# v1.net
KiCad netlist of a schematic drawn in EAGLE
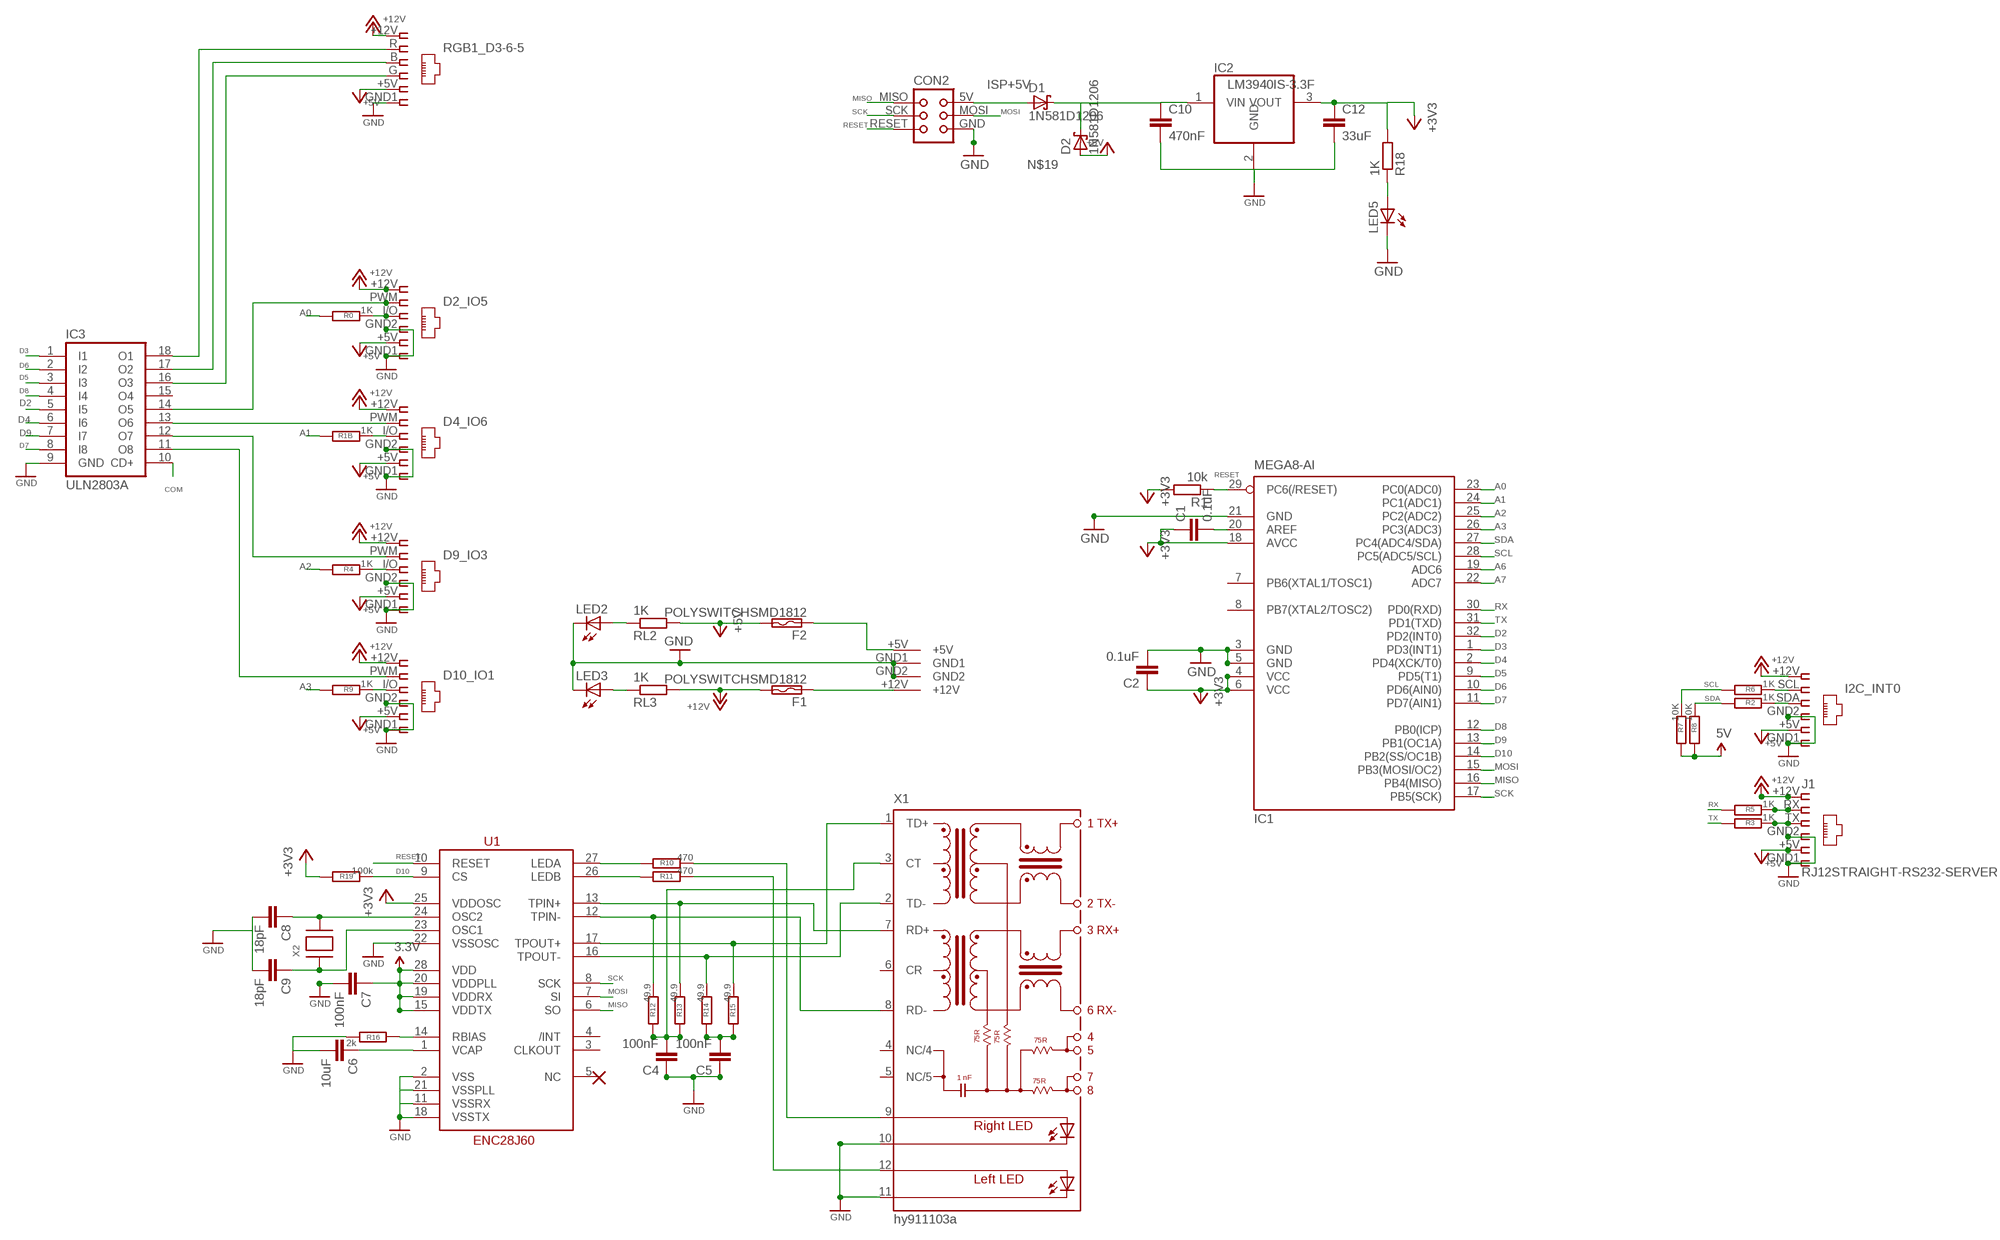
[diagram p0: schematic, sheet 1]

(export (version "E")
  (design (tool "Eeschema 10.0.6"))
  (components
    (comp (ref "C1")
      (value "0.1uF")
      (footprint "eagle-import:C1206")
      (libsource (lib "eagle-import") (part "resistor_C-EUC1206"))
    )
    (comp (ref "C2")
      (value "0.1uF")
      (footprint "eagle-import:C1206")
      (libsource (lib "eagle-import") (part "resistor_C-EUC1206"))
    )
    (comp (ref "C4")
      (value "100nF")
      (footprint "eagle-import:C1206")
      (libsource (lib "eagle-import") (part "resistor_C-EUC1206"))
    )
    (comp (ref "C5")
      (value "100nF")
      (footprint "eagle-import:C1206")
      (libsource (lib "eagle-import") (part "resistor_C-EUC1206"))
    )
    (comp (ref "C6")
      (value "10uF")
      (footprint "eagle-import:C1206")
      (libsource (lib "eagle-import") (part "resistor_C-EUC1206"))
    )
    (comp (ref "C7")
      (value "100nF")
      (footprint "eagle-import:C1206")
      (libsource (lib "eagle-import") (part "resistor_C-EUC1206"))
    )
    (comp (ref "C8")
      (value "18pF")
      (footprint "eagle-import:C1206")
      (libsource (lib "eagle-import") (part "resistor_C-EUC1206"))
    )
    (comp (ref "C9")
      (value "18pF")
      (footprint "eagle-import:C1206")
      (libsource (lib "eagle-import") (part "resistor_C-EUC1206"))
    )
    (comp (ref "C10")
      (value "470nF")
      (footprint "eagle-import:C1206")
      (libsource (lib "eagle-import") (part "C-EUC1206"))
    )
    (comp (ref "C12")
      (value "33uF")
      (footprint "eagle-import:1210")
      (libsource (lib "eagle-import") (part "CAP1210"))
    )
    (comp (ref "CON2")
      (value "TINYISPTAG")
      (footprint "eagle-import:TC2030-MCP")
      (libsource (lib "eagle-import") (part "TINYISPTAG"))
    )
    (comp (ref "D1")
      (value "1N581D1206")
      (footprint "eagle-import:LED-1206")
      (libsource (lib "eagle-import") (part "1N581D1206"))
    )
    (comp (ref "D2")
      (value "1N581D1206")
      (footprint "eagle-import:LED-1206")
      (libsource (lib "eagle-import") (part "1N581D1206"))
    )
    (comp (ref "D2_IO5")
      (value "IO5")
      (footprint "eagle-import:RJ12-STRAIGHT")
      (libsource (lib "eagle-import") (part "RJ12STRAIGHT"))
    )
    (comp (ref "D4_IO6")
      (value "IO6")
      (footprint "eagle-import:RJ12-STRAIGHT")
      (libsource (lib "eagle-import") (part "RJ12STRAIGHT"))
    )
    (comp (ref "D9_IO3")
      (value "IO3")
      (footprint "eagle-import:RJ12-STRAIGHT")
      (libsource (lib "eagle-import") (part "RJ12STRAIGHT"))
    )
    (comp (ref "D10_IO1")
      (value "IO1")
      (footprint "eagle-import:RJ12-STRAIGHT")
      (libsource (lib "eagle-import") (part "RJ12STRAIGHT"))
    )
    (comp (ref "F1")
      (value "POLYSWITCHSMD1812")
      (footprint "eagle-import:C1812")
      (libsource (lib "eagle-import") (part "POLYSWITCHSMD1812"))
    )
    (comp (ref "F2")
      (value "POLYSWITCHSMD1812")
      (footprint "eagle-import:C1812")
      (libsource (lib "eagle-import") (part "POLYSWITCHSMD1812"))
    )
    (comp (ref "I2C_INT0")
      (value "I2C")
      (footprint "eagle-import:RJ12-STRAIGHT-I2C")
      (libsource (lib "eagle-import") (part "RJ12STRAIGHT-I2C"))
    )
    (comp (ref "IC1")
      (value "MEGA8-AI")
      (footprint "eagle-import:TQFP32-08")
      (fields (field (name "MPN") "ATMEGA8-16AU"))
      (libsource (lib "eagle-import") (part "MEGA8-AI"))
    )
    (comp (ref "IC2")
      (value "LM3940IS-3.3F")
      (footprint "eagle-import:DD-3")
      (fields (field (name "MF") "TEXAS INSTRUMENTS") (field (name "MPN") "REG1117FAKTTT"))
      (libsource (lib "eagle-import") (part "LM3940IS-3.3F"))
    )
    (comp (ref "IC3")
      (value "ULN2803A")
      (footprint "eagle-import:SO18W")
      (libsource (lib "eagle-import") (part "ULN2803A"))
    )
    (comp (ref "J1")
      (value "RJ12STRAIGHT-RS232-SERVER")
      (footprint "eagle-import:RJ12-STRAIGHT-RS232")
      (libsource (lib "eagle-import") (part "RJ12STRAIGHT-RS232-SERVER"))
    )
    (comp (ref "LED2")
      (value "LED3MM")
      (footprint "eagle-import:LED3MM")
      (libsource (lib "eagle-import") (part "LED3MM"))
    )
    (comp (ref "LED3")
      (value "LED3MM")
      (footprint "eagle-import:LED3MM")
      (libsource (lib "eagle-import") (part "LED3MM"))
    )
    (comp (ref "LED5")
      (value "LED3MM")
      (footprint "eagle-import:LED3MM")
      (libsource (lib "eagle-import") (part "LED3MM"))
    )
    (comp (ref "R0")
      (value "1K")
      (footprint "eagle-import:M1206")
      (libsource (lib "eagle-import") (part "R-EU_M1206"))
    )
    (comp (ref "R1")
      (value "10k")
      (footprint "eagle-import:M1206")
      (libsource (lib "eagle-import") (part "R-EU_M1206"))
    )
    (comp (ref "R1B")
      (value "1K")
      (footprint "eagle-import:M1206")
      (libsource (lib "eagle-import") (part "R-EU_M1206"))
    )
    (comp (ref "R2")
      (value "1K")
      (footprint "eagle-import:M1206")
      (libsource (lib "eagle-import") (part "R-EU_M1206"))
    )
    (comp (ref "R3")
      (value "1K")
      (footprint "eagle-import:M1206")
      (libsource (lib "eagle-import") (part "R-EU_M1206"))
    )
    (comp (ref "R4")
      (value "1K")
      (footprint "eagle-import:M1206")
      (libsource (lib "eagle-import") (part "R-EU_M1206"))
    )
    (comp (ref "R5")
      (value "1K")
      (footprint "eagle-import:M1206")
      (libsource (lib "eagle-import") (part "R-EU_M1206"))
    )
    (comp (ref "R6")
      (value "1K")
      (footprint "eagle-import:M1206")
      (libsource (lib "eagle-import") (part "R-EU_M1206"))
    )
    (comp (ref "R7")
      (value "10K")
      (footprint "eagle-import:M1206")
      (libsource (lib "eagle-import") (part "R-EU_M1206"))
    )
    (comp (ref "R8")
      (value "10K")
      (footprint "eagle-import:M1206")
      (libsource (lib "eagle-import") (part "R-EU_M1206"))
    )
    (comp (ref "R9")
      (value "1K")
      (footprint "eagle-import:M1206")
      (libsource (lib "eagle-import") (part "R-EU_M1206"))
    )
    (comp (ref "R10")
      (value "470")
      (footprint "eagle-import:M1206")
      (libsource (lib "eagle-import") (part "R-EU_M1206"))
    )
    (comp (ref "R11")
      (value "470")
      (footprint "eagle-import:M1206")
      (libsource (lib "eagle-import") (part "R-EU_M1206"))
    )
    (comp (ref "R12")
      (value "49.9")
      (footprint "eagle-import:M1206")
      (libsource (lib "eagle-import") (part "R-EU_M1206"))
    )
    (comp (ref "R13")
      (value "49.9")
      (footprint "eagle-import:M1206")
      (libsource (lib "eagle-import") (part "R-EU_M1206"))
    )
    (comp (ref "R14")
      (value "49.9")
      (footprint "eagle-import:M1206")
      (libsource (lib "eagle-import") (part "R-EU_M1206"))
    )
    (comp (ref "R15")
      (value "49.9")
      (footprint "eagle-import:M1206")
      (libsource (lib "eagle-import") (part "R-EU_M1206"))
    )
    (comp (ref "R16")
      (value "2k")
      (footprint "eagle-import:M1206")
      (libsource (lib "eagle-import") (part "R-EU_M1206"))
    )
    (comp (ref "R18")
      (value "1K")
      (footprint "eagle-import:M1206")
      (libsource (lib "eagle-import") (part "R-EU_M1206"))
    )
    (comp (ref "R19")
      (value "100k")
      (footprint "eagle-import:M1206")
      (libsource (lib "eagle-import") (part "R-EU_M1206"))
    )
    (comp (ref "RGB1_D3-6-5")
      (value "RGB1")
      (footprint "eagle-import:RJ12-STRAIGHT-RGB")
      (libsource (lib "eagle-import") (part "RJ12STRAIGHT-RGB"))
    )
    (comp (ref "RL2")
      (value "1K")
      (footprint "eagle-import:M1206")
      (libsource (lib "eagle-import") (part "R-EU_M1206"))
    )
    (comp (ref "RL3")
      (value "1K")
      (footprint "eagle-import:M1206")
      (libsource (lib "eagle-import") (part "R-EU_M1206"))
    )
    (comp (ref "U$2")
      (value "KPJX-4S-S")
      (footprint "eagle-import:KPJX-4S-S")
      (libsource (lib "eagle-import") (part "KPJX-4S-S"))
    )
    (comp (ref "U1")
      (value "ENC28J60SO")
      (footprint "eagle-import:SO28W")
      (libsource (lib "eagle-import") (part "ENC28J60SO"))
    )
    (comp (ref "X1")
      (value "hy911103a")
      (footprint "eagle-import:J1")
      (libsource (lib "eagle-import") (part "J1011F01P"))
    )
    (comp (ref "X2")
      (value "XTALNX5032")
      (footprint "eagle-import:NX5032")
      (libsource (lib "eagle-import") (part "XTALNX5032"))
    )
  )
  (nets
    (net (code "1") (name "+3V3") (class "Default")
      (node (ref "C1") (pin "1") (pinfunction "1_1") (pintype "passive"))
      (node (ref "C12") (pin "1") (pinfunction "1_1") (pintype "passive"))
      (node (ref "C2") (pin "1") (pinfunction "1_1") (pintype "passive"))
      (node (ref "IC1") (pin "18") (pinfunction "AVCC_18") (pintype "power_in"))
      (node (ref "IC1") (pin "4") (pinfunction "VCC_4") (pintype "power_in"))
      (node (ref "IC1") (pin "6") (pinfunction "VCC_6") (pintype "power_in"))
      (node (ref "IC2") (pin "3") (pinfunction "VOUT_3") (pintype "output"))
      (node (ref "R1") (pin "2") (pinfunction "2_2") (pintype "passive"))
      (node (ref "R18") (pin "2") (pinfunction "2_2") (pintype "passive"))
      (node (ref "R19") (pin "2") (pinfunction "2_2") (pintype "passive"))
      (node (ref "U1") (pin "25") (pinfunction "VDDOSC_25") (pintype "bidirectional"))
    )
    (net (code "2") (name "+5V") (class "Default")
      (node (ref "D10_IO1") (pin "+5V") (pinfunction "5_+5V") (pintype "power_in"))
      (node (ref "D2") (pin "A") (pinfunction "A_A") (pintype "passive"))
      (node (ref "D2_IO5") (pin "+5V") (pinfunction "5_+5V") (pintype "power_in"))
      (node (ref "D4_IO6") (pin "+5V") (pinfunction "5_+5V") (pintype "power_in"))
      (node (ref "D9_IO3") (pin "+5V") (pinfunction "5_+5V") (pintype "power_in"))
      (node (ref "F2") (pin "2") (pinfunction "2_2") (pintype "passive"))
      (node (ref "I2C_INT0") (pin "+5V") (pinfunction "5_+5V") (pintype "power_in"))
      (node (ref "J1") (pin "+5V") (pinfunction "5_+5V") (pintype "power_in"))
      (node (ref "RGB1_D3-6-5") (pin "+5V") (pinfunction "5_+5V") (pintype "power_in"))
      (node (ref "RL2") (pin "2") (pinfunction "2_2") (pintype "passive"))
    )
    (net (code "3") (name "+12V") (class "Default")
      (node (ref "D10_IO1") (pin "+12V") (pinfunction "1_+12V") (pintype "power_in"))
      (node (ref "D2_IO5") (pin "+12V") (pinfunction "1_+12V") (pintype "power_in"))
      (node (ref "D4_IO6") (pin "+12V") (pinfunction "1_+12V") (pintype "power_in"))
      (node (ref "D9_IO3") (pin "+12V") (pinfunction "1_+12V") (pintype "power_in"))
      (node (ref "F1") (pin "2") (pinfunction "2_2") (pintype "passive"))
      (node (ref "I2C_INT0") (pin "+12V") (pinfunction "1_+12V") (pintype "power_in"))
      (node (ref "J1") (pin "+12V") (pinfunction "1_+12V") (pintype "power_in"))
      (node (ref "RGB1_D3-6-5") (pin "+12V") (pinfunction "1_+12V") (pintype "power_in"))
      (node (ref "RL3") (pin "2") (pinfunction "2_2") (pintype "passive"))
    )
    (net (code "4") (name "/A0") (class "Default")
      (node (ref "IC1") (pin "23") (pinfunction "PC0(ADC0)_23") (pintype "bidirectional"))
      (node (ref "R0") (pin "2") (pinfunction "2_2") (pintype "passive"))
    )
    (net (code "5") (name "/A1") (class "Default")
      (node (ref "IC1") (pin "24") (pinfunction "PC1(ADC1)_24") (pintype "bidirectional"))
      (node (ref "R1B") (pin "2") (pinfunction "2_2") (pintype "passive"))
    )
    (net (code "6") (name "/A2") (class "Default")
      (node (ref "IC1") (pin "25") (pinfunction "PC2(ADC2)_25") (pintype "bidirectional"))
      (node (ref "R4") (pin "2") (pinfunction "2_2") (pintype "passive"))
    )
    (net (code "7") (name "/A3") (class "Default")
      (node (ref "IC1") (pin "26") (pinfunction "PC3(ADC3)_26") (pintype "bidirectional"))
      (node (ref "R9") (pin "2") (pinfunction "2_2") (pintype "passive"))
    )
    (net (code "8") (name "/A6") (class "Default")
      (node (ref "IC1") (pin "19") (pinfunction "ADC6_19") (pintype "bidirectional"))
    )
    (net (code "9") (name "/A7") (class "Default")
      (node (ref "IC1") (pin "22") (pinfunction "ADC7_22") (pintype "bidirectional"))
    )
    (net (code "10") (name "/COM") (class "Default")
      (node (ref "IC3") (pin "10") (pinfunction "CD+_10") (pintype "passive"))
    )
    (net (code "11") (name "/D2") (class "Default")
      (node (ref "IC1") (pin "32") (pinfunction "PD2(INT0)_32") (pintype "bidirectional"))
      (node (ref "IC3") (pin "5") (pinfunction "I5_5") (pintype "input"))
    )
    (net (code "12") (name "/D3") (class "Default")
      (node (ref "IC1") (pin "1") (pinfunction "PD3(INT1)_1") (pintype "bidirectional"))
      (node (ref "IC3") (pin "1") (pinfunction "I1_1") (pintype "input"))
    )
    (net (code "13") (name "/D4") (class "Default")
      (node (ref "IC1") (pin "2") (pinfunction "PD4(XCK/T0)_2") (pintype "bidirectional"))
      (node (ref "IC3") (pin "6") (pinfunction "I6_6") (pintype "input"))
    )
    (net (code "14") (name "/D5") (class "Default")
      (node (ref "IC1") (pin "9") (pinfunction "PD5(T1)_9") (pintype "bidirectional"))
      (node (ref "IC3") (pin "3") (pinfunction "I3_3") (pintype "input"))
    )
    (net (code "15") (name "/D6") (class "Default")
      (node (ref "IC1") (pin "10") (pinfunction "PD6(AIN0)_10") (pintype "bidirectional"))
      (node (ref "IC3") (pin "2") (pinfunction "I2_2") (pintype "input"))
    )
    (net (code "16") (name "/D7") (class "Default")
      (node (ref "IC1") (pin "11") (pinfunction "PD7(AIN1)_11") (pintype "bidirectional"))
      (node (ref "IC3") (pin "8") (pinfunction "I8_8") (pintype "input"))
    )
    (net (code "17") (name "/D8") (class "Default")
      (node (ref "IC1") (pin "12") (pinfunction "PB0(ICP)_12") (pintype "bidirectional"))
      (node (ref "IC3") (pin "4") (pinfunction "I4_4") (pintype "input"))
    )
    (net (code "18") (name "/D9") (class "Default")
      (node (ref "IC1") (pin "13") (pinfunction "PB1(OC1A)_13") (pintype "bidirectional"))
      (node (ref "IC3") (pin "7") (pinfunction "I7_7") (pintype "input"))
    )
    (net (code "19") (name "/D10") (class "Default")
      (node (ref "IC1") (pin "14") (pinfunction "PB2(SS/OC1B)_14") (pintype "bidirectional"))
      (node (ref "R19") (pin "1") (pinfunction "1_1") (pintype "passive"))
      (node (ref "U1") (pin "9") (pinfunction "CS_9") (pintype "bidirectional"))
    )
    (net (code "20") (name "/ISP+5V") (class "Default")
      (node (ref "CON2") (pin "5V") (pinfunction "VCC_5V") (pintype "passive"))
      (node (ref "D1") (pin "A") (pinfunction "A_A") (pintype "passive"))
    )
    (net (code "21") (name "/MISO") (class "Default")
      (node (ref "CON2") (pin "MISO") (pinfunction "MISO_MISO") (pintype "passive"))
      (node (ref "IC1") (pin "16") (pinfunction "PB4(MISO)_16") (pintype "bidirectional"))
      (node (ref "U1") (pin "6") (pinfunction "SO_6") (pintype "bidirectional"))
    )
    (net (code "22") (name "/MOSI") (class "Default")
      (node (ref "CON2") (pin "MOSI") (pinfunction "MOSI_MOSI") (pintype "passive"))
      (node (ref "IC1") (pin "15") (pinfunction "PB3(MOSI/OC2)_15") (pintype "bidirectional"))
      (node (ref "U1") (pin "7") (pinfunction "SI_7") (pintype "bidirectional"))
    )
    (net (code "23") (name "/N$19") (class "Default")
      (node (ref "C10") (pin "1") (pinfunction "1_1") (pintype "passive"))
      (node (ref "D1") (pin "C") (pinfunction "C_C") (pintype "passive"))
      (node (ref "D2") (pin "C") (pinfunction "C_C") (pintype "passive"))
      (node (ref "IC2") (pin "1") (pinfunction "VIN_1") (pintype "input"))
    )
    (net (code "24") (name "/RESET") (class "Default")
      (node (ref "CON2") (pin "RESET") (pinfunction "RESET_RESET") (pintype "passive"))
      (node (ref "IC1") (pin "29") (pinfunction "PC6(/RESET)_29") (pintype "bidirectional"))
      (node (ref "R1") (pin "1") (pinfunction "1_1") (pintype "passive"))
      (node (ref "U1") (pin "10") (pinfunction "RESET_10") (pintype "bidirectional"))
    )
    (net (code "25") (name "/RX") (class "Default")
      (node (ref "IC1") (pin "30") (pinfunction "PD0(RXD)_30") (pintype "bidirectional"))
      (node (ref "R5") (pin "2") (pinfunction "2_2") (pintype "passive"))
    )
    (net (code "26") (name "/SCK") (class "Default")
      (node (ref "CON2") (pin "SCK") (pinfunction "SCK_SCK") (pintype "passive"))
      (node (ref "IC1") (pin "17") (pinfunction "PB5(SCK)_17") (pintype "bidirectional"))
      (node (ref "U1") (pin "8") (pinfunction "SCK_8") (pintype "bidirectional"))
    )
    (net (code "27") (name "/SCL") (class "Default")
      (node (ref "IC1") (pin "28") (pinfunction "PC5(ADC5/SCL)_28") (pintype "bidirectional"))
      (node (ref "R6") (pin "2") (pinfunction "2_2") (pintype "passive"))
      (node (ref "R7") (pin "1") (pinfunction "1_1") (pintype "passive"))
    )
    (net (code "28") (name "/SDA") (class "Default")
      (node (ref "IC1") (pin "27") (pinfunction "PC4(ADC4/SDA)_27") (pintype "bidirectional"))
      (node (ref "R2") (pin "2") (pinfunction "2_2") (pintype "passive"))
      (node (ref "R8") (pin "1") (pinfunction "1_1") (pintype "passive"))
    )
    (net (code "29") (name "/TX") (class "Default")
      (node (ref "IC1") (pin "31") (pinfunction "PD1(TXD)_31") (pintype "bidirectional"))
      (node (ref "R3") (pin "2") (pinfunction "2_2") (pintype "passive"))
    )
    (net (code "30") (name "3.3V") (class "Default")
      (node (ref "C7") (pin "1") (pinfunction "1_1") (pintype "passive"))
      (node (ref "U1") (pin "15") (pinfunction "VDDTX_15") (pintype "bidirectional"))
      (node (ref "U1") (pin "19") (pinfunction "VDDRX_19") (pintype "bidirectional"))
      (node (ref "U1") (pin "20") (pinfunction "VDDPLL_20") (pintype "bidirectional"))
      (node (ref "U1") (pin "28") (pinfunction "VDD_28") (pintype "bidirectional"))
    )
    (net (code "31") (name "5V") (class "Default")
      (node (ref "R7") (pin "2") (pinfunction "2_2") (pintype "passive"))
      (node (ref "R8") (pin "2") (pinfunction "2_2") (pintype "passive"))
    )
    (net (code "32") (name "GND") (class "Default")
      (node (ref "C10") (pin "2") (pinfunction "2_2") (pintype "passive"))
      (node (ref "C12") (pin "2") (pinfunction "2_2") (pintype "passive"))
      (node (ref "C2") (pin "2") (pinfunction "2_2") (pintype "passive"))
      (node (ref "C4") (pin "1") (pinfunction "1_1") (pintype "passive"))
      (node (ref "C5") (pin "1") (pinfunction "1_1") (pintype "passive"))
      (node (ref "C6") (pin "2") (pinfunction "2_2") (pintype "passive"))
      (node (ref "C7") (pin "2") (pinfunction "2_2") (pintype "passive"))
      (node (ref "C8") (pin "2") (pinfunction "2_2") (pintype "passive"))
      (node (ref "C9") (pin "2") (pinfunction "2_2") (pintype "passive"))
      (node (ref "CON2") (pin "GND") (pinfunction "GND_GND") (pintype "passive"))
      (node (ref "D10_IO1") (pin "GND1") (pinfunction "6_GND1") (pintype "power_in"))
      (node (ref "D10_IO1") (pin "GND2") (pinfunction "4_GND2") (pintype "power_in"))
      (node (ref "D2_IO5") (pin "GND1") (pinfunction "6_GND1") (pintype "power_in"))
      (node (ref "D2_IO5") (pin "GND2") (pinfunction "4_GND2") (pintype "power_in"))
      (node (ref "D4_IO6") (pin "GND1") (pinfunction "6_GND1") (pintype "power_in"))
      (node (ref "D4_IO6") (pin "GND2") (pinfunction "4_GND2") (pintype "power_in"))
      (node (ref "D9_IO3") (pin "GND1") (pinfunction "6_GND1") (pintype "power_in"))
      (node (ref "D9_IO3") (pin "GND2") (pinfunction "4_GND2") (pintype "power_in"))
      (node (ref "I2C_INT0") (pin "GND1") (pinfunction "6_GND1") (pintype "power_in"))
      (node (ref "I2C_INT0") (pin "GND2") (pinfunction "4_GND2") (pintype "power_in"))
      (node (ref "IC1") (pin "21") (pinfunction "GND_21") (pintype "power_in"))
      (node (ref "IC1") (pin "3") (pinfunction "GND_3") (pintype "power_in"))
      (node (ref "IC1") (pin "5") (pinfunction "GND_5") (pintype "power_in"))
      (node (ref "IC2") (pin "2") (pinfunction "GND_2") (pintype "power_in"))
      (node (ref "IC3") (pin "9") (pinfunction "GND_9") (pintype "power_in"))
      (node (ref "J1") (pin "GND1") (pinfunction "6_GND1") (pintype "power_in"))
      (node (ref "J1") (pin "GND2") (pinfunction "4_GND2") (pintype "power_in"))
      (node (ref "LED2") (pin "K") (pinfunction "C_K") (pintype "passive"))
      (node (ref "LED3") (pin "K") (pinfunction "C_K") (pintype "passive"))
      (node (ref "LED5") (pin "K") (pinfunction "C_K") (pintype "passive"))
      (node (ref "R16") (pin "1") (pinfunction "1_1") (pintype "passive"))
      (node (ref "RGB1_D3-6-5") (pin "GND1") (pinfunction "6_GND1") (pintype "power_in"))
      (node (ref "U$2") (pin "GND1") (pinfunction "GND1_GND1") (pintype "input"))
      (node (ref "U$2") (pin "GND2") (pinfunction "GND2_GND2") (pintype "input"))
      (node (ref "U1") (pin "11") (pinfunction "VSSRX_11") (pintype "bidirectional"))
      (node (ref "U1") (pin "18") (pinfunction "VSSTX_18") (pintype "bidirectional"))
      (node (ref "U1") (pin "2") (pinfunction "VSS_2") (pintype "bidirectional"))
      (node (ref "U1") (pin "21") (pinfunction "VSSPLL_21") (pintype "bidirectional"))
      (node (ref "U1") (pin "22") (pinfunction "VSSOSC_22") (pintype "bidirectional"))
      (node (ref "X1") (pin "10") (pinfunction "C-R_10") (pintype "passive"))
      (node (ref "X1") (pin "11") (pinfunction "C-L_11") (pintype "passive"))
    )
    (net (code "33") (name "Net-(C5-Pad2)") (class "Default")
      (node (ref "C5") (pin "2") (pinfunction "2_2") (pintype "passive"))
      (node (ref "R14") (pin "2") (pinfunction "2_2") (pintype "passive"))
      (node (ref "R15") (pin "2") (pinfunction "2_2") (pintype "passive"))
    )
    (net (code "34") (name "Net-(D2_IO5-2)") (class "Default")
      (node (ref "D2_IO5") (pin "PWM") (pinfunction "2_PWM") (pintype "bidirectional"))
      (node (ref "IC3") (pin "14") (pinfunction "O5_14") (pintype "open_collector"))
    )
    (net (code "35") (name "Net-(D2_IO5-3)") (class "Default")
      (node (ref "D2_IO5") (pin "I/O") (pinfunction "3_I/O") (pintype "bidirectional"))
      (node (ref "R0") (pin "1") (pinfunction "1_1") (pintype "passive"))
    )
    (net (code "36") (name "Net-(D4_IO6-2)") (class "Default")
      (node (ref "D4_IO6") (pin "PWM") (pinfunction "2_PWM") (pintype "bidirectional"))
      (node (ref "IC3") (pin "13") (pinfunction "O6_13") (pintype "open_collector"))
    )
    (net (code "37") (name "Net-(D4_IO6-3)") (class "Default")
      (node (ref "D4_IO6") (pin "I/O") (pinfunction "3_I/O") (pintype "bidirectional"))
      (node (ref "R1B") (pin "1") (pinfunction "1_1") (pintype "passive"))
    )
    (net (code "38") (name "Net-(D9_IO3-2)") (class "Default")
      (node (ref "D9_IO3") (pin "PWM") (pinfunction "2_PWM") (pintype "bidirectional"))
      (node (ref "IC3") (pin "12") (pinfunction "O7_12") (pintype "open_collector"))
    )
    (net (code "39") (name "Net-(D9_IO3-3)") (class "Default")
      (node (ref "D9_IO3") (pin "I/O") (pinfunction "3_I/O") (pintype "bidirectional"))
      (node (ref "R4") (pin "1") (pinfunction "1_1") (pintype "passive"))
    )
    (net (code "40") (name "Net-(D10_IO1-2)") (class "Default")
      (node (ref "D10_IO1") (pin "PWM") (pinfunction "2_PWM") (pintype "bidirectional"))
      (node (ref "IC3") (pin "11") (pinfunction "O8_11") (pintype "open_collector"))
    )
    (net (code "41") (name "Net-(D10_IO1-3)") (class "Default")
      (node (ref "D10_IO1") (pin "I/O") (pinfunction "3_I/O") (pintype "bidirectional"))
      (node (ref "R9") (pin "1") (pinfunction "1_1") (pintype "passive"))
    )
    (net (code "42") (name "Net-(F1-Pad1)") (class "Default")
      (node (ref "F1") (pin "1") (pinfunction "1_1") (pintype "passive"))
      (node (ref "U$2") (pin "+12V") (pinfunction "+12V_+12V") (pintype "power_in"))
    )
    (net (code "43") (name "Net-(F2-Pad1)") (class "Default")
      (node (ref "F2") (pin "1") (pinfunction "1_1") (pintype "passive"))
      (node (ref "U$2") (pin "+5V") (pinfunction "+5V_+5V") (pintype "power_in"))
    )
    (net (code "44") (name "Net-(I2C_INT0-2)") (class "Default")
      (node (ref "I2C_INT0") (pin "SCL") (pinfunction "2_SCL") (pintype "bidirectional"))
      (node (ref "R6") (pin "1") (pinfunction "1_1") (pintype "passive"))
    )
    (net (code "45") (name "Net-(I2C_INT0-3)") (class "Default")
      (node (ref "I2C_INT0") (pin "SDA") (pinfunction "3_SDA") (pintype "bidirectional"))
      (node (ref "R2") (pin "1") (pinfunction "1_1") (pintype "passive"))
    )
    (net (code "46") (name "Net-(IC1-AREF)") (class "Default")
      (node (ref "C1") (pin "2") (pinfunction "2_2") (pintype "passive"))
      (node (ref "IC1") (pin "20") (pinfunction "AREF_20") (pintype "passive"))
    )
    (net (code "47") (name "Net-(IC3-O1)") (class "Default")
      (node (ref "IC3") (pin "18") (pinfunction "O1_18") (pintype "open_collector"))
      (node (ref "RGB1_D3-6-5") (pin "R") (pinfunction "2_R") (pintype "bidirectional"))
    )
    (net (code "48") (name "Net-(IC3-O2)") (class "Default")
      (node (ref "IC3") (pin "17") (pinfunction "O2_17") (pintype "open_collector"))
      (node (ref "RGB1_D3-6-5") (pin "B") (pinfunction "3_B") (pintype "bidirectional"))
    )
    (net (code "49") (name "Net-(IC3-O3)") (class "Default")
      (node (ref "IC3") (pin "16") (pinfunction "O3_16") (pintype "open_collector"))
      (node (ref "RGB1_D3-6-5") (pin "G") (pinfunction "4_G") (pintype "power_in"))
    )
    (net (code "50") (name "Net-(J1-2)") (class "Default")
      (node (ref "J1") (pin "RX") (pinfunction "2_RX") (pintype "bidirectional"))
      (node (ref "R5") (pin "1") (pinfunction "1_1") (pintype "passive"))
    )
    (net (code "51") (name "Net-(J1-3)") (class "Default")
      (node (ref "J1") (pin "TX") (pinfunction "3_TX") (pintype "bidirectional"))
      (node (ref "R3") (pin "1") (pinfunction "1_1") (pintype "passive"))
    )
    (net (code "52") (name "Net-(LED2-PadA)") (class "Default")
      (node (ref "LED2") (pin "A") (pinfunction "A_A") (pintype "passive"))
      (node (ref "RL2") (pin "1") (pinfunction "1_1") (pintype "passive"))
    )
    (net (code "53") (name "Net-(LED3-PadA)") (class "Default")
      (node (ref "LED3") (pin "A") (pinfunction "A_A") (pintype "passive"))
      (node (ref "RL3") (pin "1") (pinfunction "1_1") (pintype "passive"))
    )
    (net (code "54") (name "Net-(LED5-PadA)") (class "Default")
      (node (ref "LED5") (pin "A") (pinfunction "A_A") (pintype "passive"))
      (node (ref "R18") (pin "1") (pinfunction "1_1") (pintype "passive"))
    )
    (net (code "55") (name "Net-(U1-LEDA)") (class "Default")
      (node (ref "R10") (pin "2") (pinfunction "2_2") (pintype "passive"))
      (node (ref "U1") (pin "27") (pinfunction "LEDA_27") (pintype "bidirectional"))
    )
    (net (code "56") (name "Net-(U1-LEDB)") (class "Default")
      (node (ref "R11") (pin "2") (pinfunction "2_2") (pintype "passive"))
      (node (ref "U1") (pin "26") (pinfunction "LEDB_26") (pintype "bidirectional"))
    )
    (net (code "57") (name "Net-(U1-OSC1)") (class "Default")
      (node (ref "C9") (pin "1") (pinfunction "1_1") (pintype "passive"))
      (node (ref "U1") (pin "23") (pinfunction "OSC1_23") (pintype "bidirectional"))
      (node (ref "X2") (pin "P$1") (pinfunction "P$1_P$1") (pintype "bidirectional"))
    )
    (net (code "58") (name "Net-(U1-OSC2)") (class "Default")
      (node (ref "C8") (pin "1") (pinfunction "1_1") (pintype "passive"))
      (node (ref "U1") (pin "24") (pinfunction "OSC2_24") (pintype "bidirectional"))
      (node (ref "X2") (pin "P$2") (pinfunction "P$2_P$2") (pintype "bidirectional"))
    )
    (net (code "59") (name "Net-(U1-RBIAS)") (class "Default")
      (node (ref "R16") (pin "2") (pinfunction "2_2") (pintype "passive"))
      (node (ref "U1") (pin "14") (pinfunction "RBIAS_14") (pintype "bidirectional"))
    )
    (net (code "60") (name "Net-(U1-TPIN+)") (class "Default")
      (node (ref "R13") (pin "1") (pinfunction "1_1") (pintype "passive"))
      (node (ref "U1") (pin "13") (pinfunction "TPIN+_13") (pintype "bidirectional"))
      (node (ref "X1") (pin "7") (pinfunction "RD+_7") (pintype "input"))
    )
    (net (code "61") (name "Net-(U1-TPIN-)") (class "Default")
      (node (ref "R12") (pin "1") (pinfunction "1_1") (pintype "passive"))
      (node (ref "U1") (pin "12") (pinfunction "TPIN-_12") (pintype "bidirectional"))
      (node (ref "X1") (pin "8") (pinfunction "RD-_8") (pintype "input"))
    )
    (net (code "62") (name "Net-(U1-TPOUT+)") (class "Default")
      (node (ref "R15") (pin "1") (pinfunction "1_1") (pintype "passive"))
      (node (ref "U1") (pin "17") (pinfunction "TPOUT+_17") (pintype "bidirectional"))
      (node (ref "X1") (pin "1") (pinfunction "TD+_1") (pintype "input"))
    )
    (net (code "63") (name "Net-(U1-TPOUT-)") (class "Default")
      (node (ref "R14") (pin "1") (pinfunction "1_1") (pintype "passive"))
      (node (ref "U1") (pin "16") (pinfunction "TPOUT-_16") (pintype "bidirectional"))
      (node (ref "X1") (pin "2") (pinfunction "TD-_2") (pintype "input"))
    )
    (net (code "64") (name "Net-(U1-VCAP)") (class "Default")
      (node (ref "C6") (pin "1") (pinfunction "1_1") (pintype "passive"))
      (node (ref "U1") (pin "1") (pinfunction "VCAP_1") (pintype "bidirectional"))
    )
    (net (code "65") (name "Net-(X1-A-R)") (class "Default")
      (node (ref "R10") (pin "1") (pinfunction "1_1") (pintype "passive"))
      (node (ref "X1") (pin "9") (pinfunction "A-R_9") (pintype "passive"))
    )
    (net (code "66") (name "Net-(X1-AL)") (class "Default")
      (node (ref "R11") (pin "1") (pinfunction "1_1") (pintype "passive"))
      (node (ref "X1") (pin "12") (pinfunction "AL_12") (pintype "passive"))
    )
    (net (code "67") (name "Net-(X1-CT)") (class "Default")
      (node (ref "C4") (pin "2") (pinfunction "2_2") (pintype "passive"))
      (node (ref "R12") (pin "2") (pinfunction "2_2") (pintype "passive"))
      (node (ref "R13") (pin "2") (pinfunction "2_2") (pintype "passive"))
      (node (ref "X1") (pin "3") (pinfunction "CT_3") (pintype "input"))
    )
    (net (code "68") (name "unconnected-(IC1-PB6(XTAL1{slash}TOSC1)-Pad7)") (class "Default")
      (node (ref "IC1") (pin "7") (pinfunction "PB6(XTAL1/TOSC1)_7") (pintype "bidirectional"))
    )
    (net (code "69") (name "unconnected-(IC1-PB7(XTAL2{slash}TOSC2)-Pad8)") (class "Default")
      (node (ref "IC1") (pin "8") (pinfunction "PB7(XTAL2/TOSC2)_8") (pintype "bidirectional"))
    )
    (net (code "70") (name "unconnected-(IC3-O4-Pad15)") (class "Default")
      (node (ref "IC3") (pin "15") (pinfunction "O4_15") (pintype "open_collector"))
    )
    (net (code "71") (name "unconnected-(U1-CLKOUT-Pad3)") (class "Default")
      (node (ref "U1") (pin "3") (pinfunction "CLKOUT_3") (pintype "bidirectional"))
    )
    (net (code "72") (name "unconnected-(U1-NC-Pad5)") (class "Default")
      (node (ref "U1") (pin "5") (pinfunction "NC_5") (pintype "bidirectional"))
    )
    (net (code "73") (name "unconnected-(U1-{slash}INT-Pad4)") (class "Default")
      (node (ref "U1") (pin "4") (pinfunction "/INT_4") (pintype "bidirectional"))
    )
    (net (code "74") (name "unconnected-(X1-CR-Pad6)") (class "Default")
      (node (ref "X1") (pin "6") (pinfunction "CR_6") (pintype "input"))
    )
    (net (code "75") (name "unconnected-(X1-NC{slash}4-Pad4)") (class "Default")
      (node (ref "X1") (pin "4") (pinfunction "NC/4_4") (pintype "input"))
    )
    (net (code "76") (name "unconnected-(X1-NC{slash}5-Pad5)") (class "Default")
      (node (ref "X1") (pin "5") (pinfunction "NC/5_5") (pintype "input"))
    )
  )
)
